# POWER.net
KiCad netlist of a schematic drawn in Altium Designer
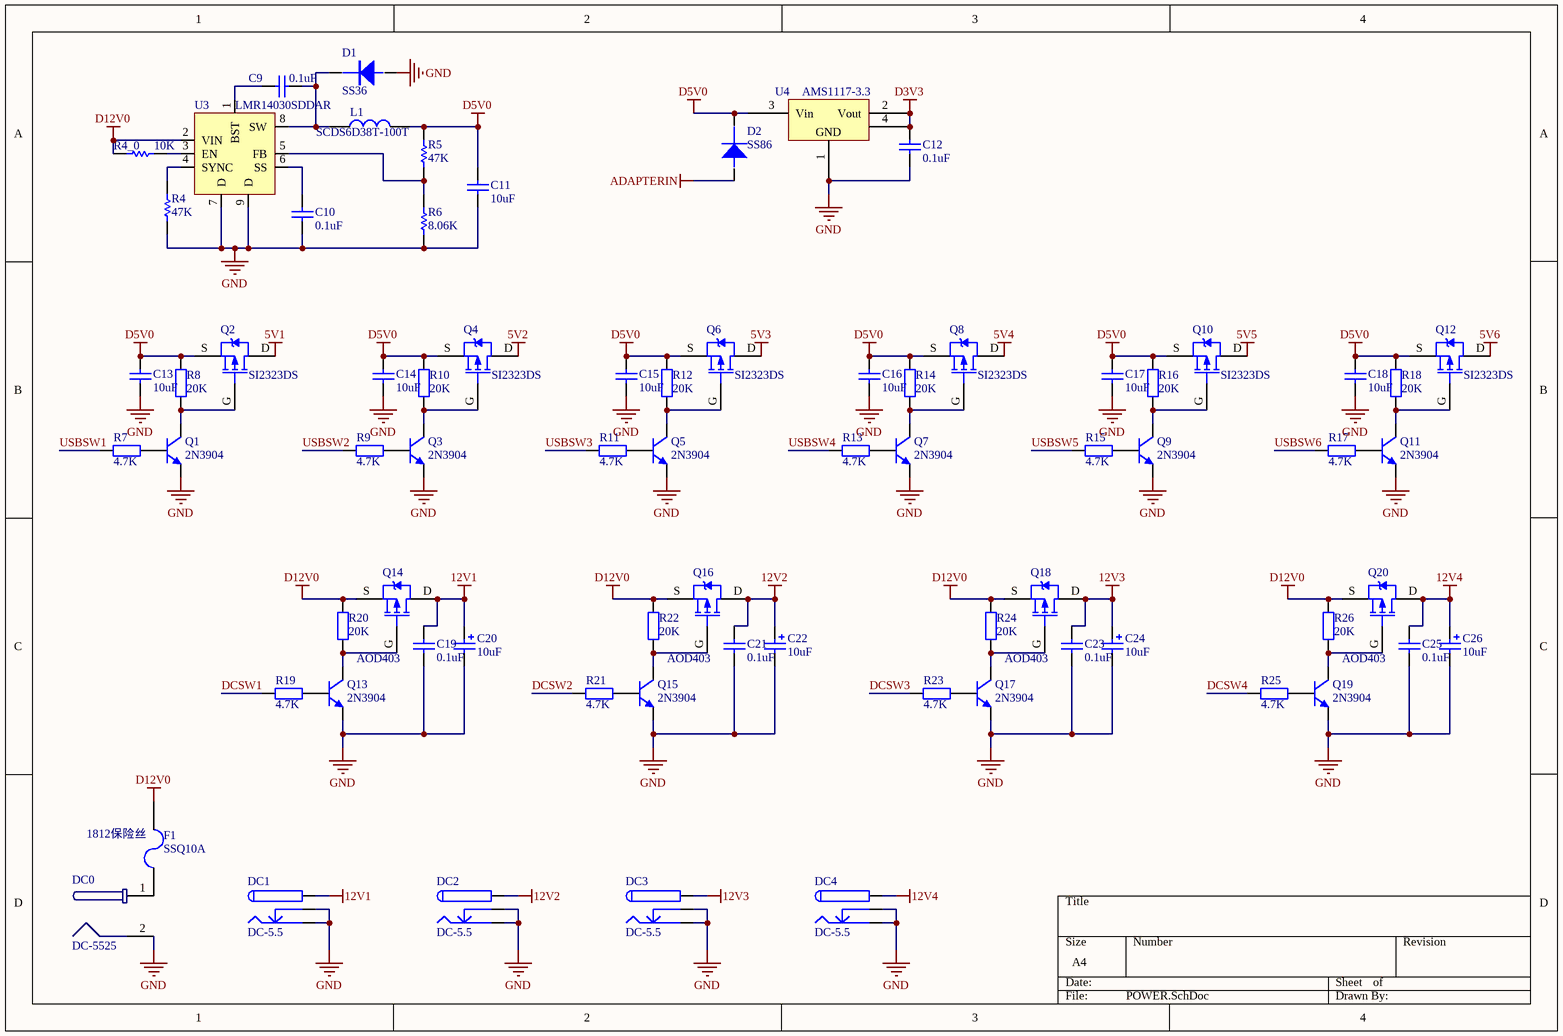
[diagram p0: POWER.SchDoc]

(export (version "E")
  (design (tool "Eeschema 10.0.6"))
  (components
    (comp (ref "C9")
      (value "0.1uF")
      (footprint "0603C")
      (description "Capacitor")
      (fields (field (name "PUBLISHER") "Altium Limited"))
      (libsource (lib "JL_SCH") (part "Cap"))
    )
    (comp (ref "C10")
      (value "0.1uF")
      (footprint "0603C")
      (description "Capacitor")
      (fields (field (name "PUBLISHER") "Altium Limited"))
      (libsource (lib "JL_SCH") (part "Cap"))
    )
    (comp (ref "C11")
      (value "10uF")
      (footprint "3216")
      (description "Capacitor")
      (fields (field (name "PUBLISHER") "Altium Limited"))
      (libsource (lib "JL_SCH") (part "Cap"))
    )
    (comp (ref "C12")
      (value "0.1uF")
      (footprint "0603C")
      (description "Capacitor")
      (fields (field (name "PUBLISHER") "Altium Limited"))
      (libsource (lib "JL_SCH") (part "Cap"))
    )
    (comp (ref "C13")
      (value "10uF")
      (footprint "3216")
      (description "Capacitor")
      (fields (field (name "PUBLISHER") "Altium Limited"))
      (libsource (lib "JL_SCH") (part "Cap"))
    )
    (comp (ref "C14")
      (value "10uF")
      (footprint "3216")
      (description "Capacitor")
      (fields (field (name "PUBLISHER") "Altium Limited"))
      (libsource (lib "JL_SCH") (part "Cap"))
    )
    (comp (ref "C15")
      (value "10uF")
      (footprint "3216")
      (description "Capacitor")
      (fields (field (name "PUBLISHER") "Altium Limited"))
      (libsource (lib "JL_SCH") (part "Cap"))
    )
    (comp (ref "C16")
      (value "10uF")
      (footprint "3216")
      (description "Capacitor")
      (fields (field (name "PUBLISHER") "Altium Limited"))
      (libsource (lib "JL_SCH") (part "Cap"))
    )
    (comp (ref "C17")
      (value "10uF")
      (footprint "3216")
      (description "Capacitor")
      (fields (field (name "PUBLISHER") "Altium Limited"))
      (libsource (lib "JL_SCH") (part "Cap"))
    )
    (comp (ref "C18")
      (value "10uF")
      (footprint "3216")
      (description "Capacitor")
      (fields (field (name "PUBLISHER") "Altium Limited"))
      (libsource (lib "JL_SCH") (part "Cap"))
    )
    (comp (ref "C19")
      (value "0.1uF")
      (footprint "0603C")
      (description "Capacitor")
      (fields (field (name "PUBLISHER") "Altium Limited"))
      (libsource (lib "JL_SCH") (part "Cap"))
    )
    (comp (ref "C20")
      (value "10uF")
      (footprint "3216")
      (description "Polarized Capacitor (Radial)")
      (fields (field (name "PUBLISHER") "Altium Limited"))
      (libsource (lib "JL_SCH") (part "Cap Pol1"))
    )
    (comp (ref "C21")
      (value "0.1uF")
      (footprint "0603C")
      (description "Capacitor")
      (fields (field (name "PUBLISHER") "Altium Limited"))
      (libsource (lib "JL_SCH") (part "Cap"))
    )
    (comp (ref "C22")
      (value "10uF")
      (footprint "3216")
      (description "Polarized Capacitor (Radial)")
      (fields (field (name "PUBLISHER") "Altium Limited"))
      (libsource (lib "JL_SCH") (part "Cap Pol1"))
    )
    (comp (ref "C23")
      (value "0.1uF")
      (footprint "0603C")
      (description "Capacitor")
      (fields (field (name "PUBLISHER") "Altium Limited"))
      (libsource (lib "JL_SCH") (part "Cap"))
    )
    (comp (ref "C24")
      (value "10uF")
      (footprint "3216")
      (description "Polarized Capacitor (Radial)")
      (fields (field (name "PUBLISHER") "Altium Limited"))
      (libsource (lib "JL_SCH") (part "Cap Pol1"))
    )
    (comp (ref "C25")
      (value "0.1uF")
      (footprint "0603C")
      (description "Capacitor")
      (fields (field (name "PUBLISHER") "Altium Limited"))
      (libsource (lib "JL_SCH") (part "Cap"))
    )
    (comp (ref "C26")
      (value "10uF")
      (footprint "3216")
      (description "Polarized Capacitor (Radial)")
      (fields (field (name "PUBLISHER") "Altium Limited"))
      (libsource (lib "JL_SCH") (part "Cap Pol1"))
    )
    (comp (ref "D1")
      (value "SS36")
      (footprint "DO-214AC")
      (description "二极管，3A")
      (libsource (lib "平台原理图symbol图库V1.0") (part "SS36"))
    )
    (comp (ref "D2")
      (value "SS86")
      (footprint "SS34")
      (description "Diode,Vr=60V,If=8.0A,Vf=0.75V,DO-214AB,SS86,8.13x6.22x2.62mm")
      (libsource (lib "Diode") (part "SS86"))
    )
    (comp (ref "DC0") (value "DC-5525") (footprint "DC-5525") (libsource (lib "JL_SCH") (part "DC-5525")))
    (comp (ref "DC1") (value "DC-5.5") (footprint "DC_5.5MM") (libsource (lib "JL_SCH") (part "POWER-5.5")))
    (comp (ref "DC2") (value "DC-5.5") (footprint "DC_5.5MM") (libsource (lib "JL_SCH") (part "POWER-5.5")))
    (comp (ref "DC3") (value "DC-5.5") (footprint "DC_5.5MM") (libsource (lib "JL_SCH") (part "POWER-5.5")))
    (comp (ref "DC4") (value "DC-5.5") (footprint "DC_5.5MM") (libsource (lib "JL_SCH") (part "POWER-5.5")))
    (comp (ref "F1")
      (value "SSQ10A")
      (footprint "1812R")
      (description "Fuse")
      (libsource (lib "JL_SCH") (part "FUSE2"))
    )
    (comp (ref "L1")
      (value "SCDS6D38T-100T")
      (footprint "CD845")
      (description "电感")
      (libsource (lib "TYW_Discrete") (part "SPM6530"))
    )
    (comp (ref "Q1")
      (value "2N3904")
      (footprint "SOT-23")
      (description "NPN General Purpose Amplifier")
      (fields (field (name "PUBLISHER") "Altium Limited"))
      (libsource (lib "JL_SCH") (part "2N3904"))
    )
    (comp (ref "Q2") (value "SI2323DS") (footprint "SIMOS") (libsource (lib "JL_SCH") (part "SI2323")))
    (comp (ref "Q3")
      (value "2N3904")
      (footprint "SOT-23")
      (description "NPN General Purpose Amplifier")
      (fields (field (name "PUBLISHER") "Altium Limited"))
      (libsource (lib "JL_SCH") (part "2N3904"))
    )
    (comp (ref "Q4") (value "SI2323DS") (footprint "SIMOS") (libsource (lib "JL_SCH") (part "SI2323")))
    (comp (ref "Q5")
      (value "2N3904")
      (footprint "SOT-23")
      (description "NPN General Purpose Amplifier")
      (fields (field (name "PUBLISHER") "Altium Limited"))
      (libsource (lib "JL_SCH") (part "2N3904"))
    )
    (comp (ref "Q6") (value "SI2323DS") (footprint "SIMOS") (libsource (lib "JL_SCH") (part "SI2323")))
    (comp (ref "Q7")
      (value "2N3904")
      (footprint "SOT-23")
      (description "NPN General Purpose Amplifier")
      (fields (field (name "PUBLISHER") "Altium Limited"))
      (libsource (lib "JL_SCH") (part "2N3904"))
    )
    (comp (ref "Q8") (value "SI2323DS") (footprint "SIMOS") (libsource (lib "JL_SCH") (part "SI2323")))
    (comp (ref "Q9")
      (value "2N3904")
      (footprint "SOT-23")
      (description "NPN General Purpose Amplifier")
      (fields (field (name "PUBLISHER") "Altium Limited"))
      (libsource (lib "JL_SCH") (part "2N3904"))
    )
    (comp (ref "Q10") (value "SI2323DS") (footprint "SIMOS") (libsource (lib "JL_SCH") (part "SI2323")))
    (comp (ref "Q11")
      (value "2N3904")
      (footprint "SOT-23")
      (description "NPN General Purpose Amplifier")
      (fields (field (name "PUBLISHER") "Altium Limited"))
      (libsource (lib "JL_SCH") (part "2N3904"))
    )
    (comp (ref "Q12") (value "SI2323DS") (footprint "SIMOS") (libsource (lib "JL_SCH") (part "SI2323")))
    (comp (ref "Q13")
      (value "2N3904")
      (footprint "SOT-23")
      (description "NPN General Purpose Amplifier")
      (fields (field (name "PUBLISHER") "Altium Limited"))
      (libsource (lib "JL_SCH") (part "2N3904"))
    )
    (comp (ref "Q14") (value "AOD403") (footprint "TO-252") (libsource (lib "JL_SCH") (part "SI2323")))
    (comp (ref "Q15")
      (value "2N3904")
      (footprint "SOT-23")
      (description "NPN General Purpose Amplifier")
      (fields (field (name "PUBLISHER") "Altium Limited"))
      (libsource (lib "JL_SCH") (part "2N3904"))
    )
    (comp (ref "Q16") (value "AOD403") (footprint "TO-252") (libsource (lib "JL_SCH") (part "SI2323")))
    (comp (ref "Q17")
      (value "2N3904")
      (footprint "SOT-23")
      (description "NPN General Purpose Amplifier")
      (fields (field (name "PUBLISHER") "Altium Limited"))
      (libsource (lib "JL_SCH") (part "2N3904"))
    )
    (comp (ref "Q18") (value "AOD403") (footprint "TO-252") (libsource (lib "JL_SCH") (part "SI2323")))
    (comp (ref "Q19")
      (value "2N3904")
      (footprint "SOT-23")
      (description "NPN General Purpose Amplifier")
      (fields (field (name "PUBLISHER") "Altium Limited"))
      (libsource (lib "JL_SCH") (part "2N3904"))
    )
    (comp (ref "Q20") (value "AOD403") (footprint "TO-252") (libsource (lib "JL_SCH") (part "SI2323")))
    (comp (ref "R4")
      (value "47K")
      (footprint "0603R")
      (description "贴片电阻")
      (fields (field (name "PUBLISHER") "Altium Limited"))
      (libsource (lib "JL_SCH") (part "Res"))
    )
    (comp (ref "R4_0")
      (value "10K")
      (footprint "0603R")
      (description "贴片电阻")
      (fields (field (name "PUBLISHER") "Altium Limited"))
      (libsource (lib "JL_SCH") (part "Res"))
    )
    (comp (ref "R5")
      (value "47K")
      (footprint "0603R")
      (description "贴片电阻")
      (fields (field (name "PUBLISHER") "Altium Limited"))
      (libsource (lib "JL_SCH") (part "Res"))
    )
    (comp (ref "R6")
      (value "8.06K")
      (footprint "0603R")
      (description "贴片电阻")
      (fields (field (name "PUBLISHER") "Altium Limited"))
      (libsource (lib "JL_SCH") (part "Res"))
    )
    (comp (ref "R7")
      (value "4.7K")
      (footprint "0603R")
      (description "Resistor")
      (fields (field (name "PUBLISHER") "Altium Limited"))
      (libsource (lib "") (part "RES_1"))
    )
    (comp (ref "R8")
      (value "20K")
      (footprint "0603R")
      (description "Resistor")
      (fields (field (name "PUBLISHER") "Altium Limited"))
      (libsource (lib "Crazy_PCB") (part "RES"))
    )
    (comp (ref "R9")
      (value "4.7K")
      (footprint "0603R")
      (description "Resistor")
      (fields (field (name "PUBLISHER") "Altium Limited"))
      (libsource (lib "") (part "RES_1"))
    )
    (comp (ref "R10")
      (value "20K")
      (footprint "0603R")
      (description "Resistor")
      (fields (field (name "PUBLISHER") "Altium Limited"))
      (libsource (lib "Crazy_PCB") (part "RES"))
    )
    (comp (ref "R11")
      (value "4.7K")
      (footprint "0603R")
      (description "Resistor")
      (fields (field (name "PUBLISHER") "Altium Limited"))
      (libsource (lib "") (part "RES_1"))
    )
    (comp (ref "R12")
      (value "20K")
      (footprint "0603R")
      (description "Resistor")
      (fields (field (name "PUBLISHER") "Altium Limited"))
      (libsource (lib "Crazy_PCB") (part "RES"))
    )
    (comp (ref "R13")
      (value "4.7K")
      (footprint "0603R")
      (description "Resistor")
      (fields (field (name "PUBLISHER") "Altium Limited"))
      (libsource (lib "") (part "RES_1"))
    )
    (comp (ref "R14")
      (value "20K")
      (footprint "0603R")
      (description "Resistor")
      (fields (field (name "PUBLISHER") "Altium Limited"))
      (libsource (lib "Crazy_PCB") (part "RES"))
    )
    (comp (ref "R15")
      (value "4.7K")
      (footprint "0603R")
      (description "Resistor")
      (fields (field (name "PUBLISHER") "Altium Limited"))
      (libsource (lib "") (part "RES_1"))
    )
    (comp (ref "R16")
      (value "20K")
      (footprint "0603R")
      (description "Resistor")
      (fields (field (name "PUBLISHER") "Altium Limited"))
      (libsource (lib "Crazy_PCB") (part "RES"))
    )
    (comp (ref "R17")
      (value "4.7K")
      (footprint "0603R")
      (description "Resistor")
      (fields (field (name "PUBLISHER") "Altium Limited"))
      (libsource (lib "") (part "RES_1"))
    )
    (comp (ref "R18")
      (value "20K")
      (footprint "0603R")
      (description "Resistor")
      (fields (field (name "PUBLISHER") "Altium Limited"))
      (libsource (lib "Crazy_PCB") (part "RES"))
    )
    (comp (ref "R19")
      (value "4.7K")
      (footprint "0603R")
      (description "Resistor")
      (fields (field (name "PUBLISHER") "Altium Limited"))
      (libsource (lib "") (part "RES_1"))
    )
    (comp (ref "R20")
      (value "20K")
      (footprint "0603R")
      (description "Resistor")
      (fields (field (name "PUBLISHER") "Altium Limited"))
      (libsource (lib "Crazy_PCB") (part "RES"))
    )
    (comp (ref "R21")
      (value "4.7K")
      (footprint "0603R")
      (description "Resistor")
      (fields (field (name "PUBLISHER") "Altium Limited"))
      (libsource (lib "") (part "RES_1"))
    )
    (comp (ref "R22")
      (value "20K")
      (footprint "0603R")
      (description "Resistor")
      (fields (field (name "PUBLISHER") "Altium Limited"))
      (libsource (lib "Crazy_PCB") (part "RES"))
    )
    (comp (ref "R23")
      (value "4.7K")
      (footprint "0603R")
      (description "Resistor")
      (fields (field (name "PUBLISHER") "Altium Limited"))
      (libsource (lib "") (part "RES_1"))
    )
    (comp (ref "R24")
      (value "20K")
      (footprint "0603R")
      (description "Resistor")
      (fields (field (name "PUBLISHER") "Altium Limited"))
      (libsource (lib "Crazy_PCB") (part "RES"))
    )
    (comp (ref "R25")
      (value "4.7K")
      (footprint "0603R")
      (description "Resistor")
      (fields (field (name "PUBLISHER") "Altium Limited"))
      (libsource (lib "") (part "RES_1"))
    )
    (comp (ref "R26")
      (value "20K")
      (footprint "0603R")
      (description "Resistor")
      (fields (field (name "PUBLISHER") "Altium Limited"))
      (libsource (lib "Crazy_PCB") (part "RES"))
    )
    (comp (ref "U3")
      (value "LMR14030SDDAR")
      (footprint "LMR14030")
      (libsource (lib "JL_SCH") (part "LMR14030"))
    )
    (comp (ref "U4") (value "AMS1117-3.3") (footprint "SOT223") (libsource (lib "JL_SCH") (part "SPX1117")))
  )
  (nets
    (net (code "1") (name "/DCSW1") (class "Default")
      (node (ref "R19") (pin "1") (pinfunction "1_1") (pintype "passive"))
    )
    (net (code "2") (name "/DCSW2") (class "Default")
      (node (ref "R21") (pin "1") (pinfunction "1_1") (pintype "passive"))
    )
    (net (code "3") (name "/DCSW3") (class "Default")
      (node (ref "R23") (pin "1") (pinfunction "1_1") (pintype "passive"))
    )
    (net (code "4") (name "/DCSW4") (class "Default")
      (node (ref "R25") (pin "1") (pinfunction "1_1") (pintype "passive"))
    )
    (net (code "5") (name "/USBSW1") (class "Default")
      (node (ref "R7") (pin "1") (pinfunction "1_1") (pintype "passive"))
    )
    (net (code "6") (name "/USBSW2") (class "Default")
      (node (ref "R9") (pin "1") (pinfunction "1_1") (pintype "passive"))
    )
    (net (code "7") (name "/USBSW3") (class "Default")
      (node (ref "R11") (pin "1") (pinfunction "1_1") (pintype "passive"))
    )
    (net (code "8") (name "/USBSW4") (class "Default")
      (node (ref "R13") (pin "1") (pinfunction "1_1") (pintype "passive"))
    )
    (net (code "9") (name "/USBSW5") (class "Default")
      (node (ref "R15") (pin "1") (pinfunction "1_1") (pintype "passive"))
    )
    (net (code "10") (name "/USBSW6") (class "Default")
      (node (ref "R17") (pin "1") (pinfunction "1_1") (pintype "passive"))
    )
    (net (code "11") (name "5V1") (class "Default")
      (node (ref "Q2") (pin "D") (pinfunction "D_D") (pintype "passive"))
    )
    (net (code "12") (name "5V2") (class "Default")
      (node (ref "Q4") (pin "D") (pinfunction "D_D") (pintype "passive"))
    )
    (net (code "13") (name "5V3") (class "Default")
      (node (ref "Q6") (pin "D") (pinfunction "D_D") (pintype "passive"))
    )
    (net (code "14") (name "5V4") (class "Default")
      (node (ref "Q8") (pin "D") (pinfunction "D_D") (pintype "passive"))
    )
    (net (code "15") (name "5V5") (class "Default")
      (node (ref "Q10") (pin "D") (pinfunction "D_D") (pintype "passive"))
    )
    (net (code "16") (name "5V6") (class "Default")
      (node (ref "Q12") (pin "D") (pinfunction "D_D") (pintype "passive"))
    )
    (net (code "17") (name "12V1") (class "Default")
      (node (ref "C19") (pin "1") (pinfunction "1_1") (pintype "passive"))
      (node (ref "C20") (pin "1") (pinfunction "1_1") (pintype "passive"))
      (node (ref "DC1") (pin "1") (pinfunction "1_1") (pintype "power_in"))
      (node (ref "Q14") (pin "D") (pinfunction "D_D") (pintype "passive"))
    )
    (net (code "18") (name "12V2") (class "Default")
      (node (ref "C21") (pin "1") (pinfunction "1_1") (pintype "passive"))
      (node (ref "C22") (pin "1") (pinfunction "1_1") (pintype "passive"))
      (node (ref "DC2") (pin "1") (pinfunction "1_1") (pintype "power_in"))
      (node (ref "Q16") (pin "D") (pinfunction "D_D") (pintype "passive"))
    )
    (net (code "19") (name "12V3") (class "Default")
      (node (ref "C23") (pin "1") (pinfunction "1_1") (pintype "passive"))
      (node (ref "C24") (pin "1") (pinfunction "1_1") (pintype "passive"))
      (node (ref "DC3") (pin "1") (pinfunction "1_1") (pintype "power_in"))
      (node (ref "Q18") (pin "D") (pinfunction "D_D") (pintype "passive"))
    )
    (net (code "20") (name "12V4") (class "Default")
      (node (ref "C25") (pin "1") (pinfunction "1_1") (pintype "passive"))
      (node (ref "C26") (pin "1") (pinfunction "1_1") (pintype "passive"))
      (node (ref "DC4") (pin "1") (pinfunction "1_1") (pintype "power_in"))
      (node (ref "Q20") (pin "D") (pinfunction "D_D") (pintype "passive"))
    )
    (net (code "21") (name "ADAPTERIN") (class "Default")
      (node (ref "D2") (pin "1") (pinfunction "1_1") (pintype "passive"))
    )
    (net (code "22") (name "D3V3") (class "Default")
      (node (ref "C12") (pin "2") (pinfunction "2_2") (pintype "passive"))
      (node (ref "U4") (pin "2") (pinfunction "Vout_2") (pintype "passive"))
      (node (ref "U4") (pin "4") (pintype "passive"))
    )
    (net (code "23") (name "D5V0") (class "Default")
      (node (ref "C11") (pin "1") (pinfunction "1_1") (pintype "passive"))
      (node (ref "C13") (pin "1") (pinfunction "1_1") (pintype "passive"))
      (node (ref "C14") (pin "1") (pinfunction "1_1") (pintype "passive"))
      (node (ref "C15") (pin "1") (pinfunction "1_1") (pintype "passive"))
      (node (ref "C16") (pin "1") (pinfunction "1_1") (pintype "passive"))
      (node (ref "C17") (pin "1") (pinfunction "1_1") (pintype "passive"))
      (node (ref "C18") (pin "1") (pinfunction "1_1") (pintype "passive"))
      (node (ref "D2") (pin "2") (pinfunction "2_2") (pintype "passive"))
      (node (ref "L1") (pin "2") (pinfunction "2_2") (pintype "passive"))
      (node (ref "Q10") (pin "S") (pinfunction "S_S") (pintype "passive"))
      (node (ref "Q12") (pin "S") (pinfunction "S_S") (pintype "passive"))
      (node (ref "Q2") (pin "S") (pinfunction "S_S") (pintype "passive"))
      (node (ref "Q4") (pin "S") (pinfunction "S_S") (pintype "passive"))
      (node (ref "Q6") (pin "S") (pinfunction "S_S") (pintype "passive"))
      (node (ref "Q8") (pin "S") (pinfunction "S_S") (pintype "passive"))
      (node (ref "R10") (pin "1") (pinfunction "1_1") (pintype "passive"))
      (node (ref "R12") (pin "1") (pinfunction "1_1") (pintype "passive"))
      (node (ref "R14") (pin "1") (pinfunction "1_1") (pintype "passive"))
      (node (ref "R16") (pin "1") (pinfunction "1_1") (pintype "passive"))
      (node (ref "R18") (pin "1") (pinfunction "1_1") (pintype "passive"))
      (node (ref "R5") (pin "1") (pinfunction "1_1") (pintype "passive"))
      (node (ref "R8") (pin "1") (pinfunction "1_1") (pintype "passive"))
      (node (ref "U4") (pin "3") (pinfunction "Vin_3") (pintype "passive"))
    )
    (net (code "24") (name "D12V0") (class "Default")
      (node (ref "F1") (pin "2") (pinfunction "2_2") (pintype "passive"))
      (node (ref "Q14") (pin "S") (pinfunction "S_S") (pintype "passive"))
      (node (ref "Q16") (pin "S") (pinfunction "S_S") (pintype "passive"))
      (node (ref "Q18") (pin "S") (pinfunction "S_S") (pintype "passive"))
      (node (ref "Q20") (pin "S") (pinfunction "S_S") (pintype "passive"))
      (node (ref "R20") (pin "1") (pinfunction "1_1") (pintype "passive"))
      (node (ref "R22") (pin "1") (pinfunction "1_1") (pintype "passive"))
      (node (ref "R24") (pin "1") (pinfunction "1_1") (pintype "passive"))
      (node (ref "R26") (pin "1") (pinfunction "1_1") (pintype "passive"))
      (node (ref "R4_0") (pin "2") (pinfunction "2_2") (pintype "passive"))
      (node (ref "U3") (pin "2") (pinfunction "VIN_2") (pintype "passive"))
    )
    (net (code "25") (name "GND") (class "Default")
      (node (ref "C10") (pin "1") (pinfunction "1_1") (pintype "passive"))
      (node (ref "C11") (pin "2") (pinfunction "2_2") (pintype "passive"))
      (node (ref "C12") (pin "1") (pinfunction "1_1") (pintype "passive"))
      (node (ref "C13") (pin "2") (pinfunction "2_2") (pintype "passive"))
      (node (ref "C14") (pin "2") (pinfunction "2_2") (pintype "passive"))
      (node (ref "C15") (pin "2") (pinfunction "2_2") (pintype "passive"))
      (node (ref "C16") (pin "2") (pinfunction "2_2") (pintype "passive"))
      (node (ref "C17") (pin "2") (pinfunction "2_2") (pintype "passive"))
      (node (ref "C18") (pin "2") (pinfunction "2_2") (pintype "passive"))
      (node (ref "C19") (pin "2") (pinfunction "2_2") (pintype "passive"))
      (node (ref "C20") (pin "2") (pinfunction "2_2") (pintype "passive"))
      (node (ref "C21") (pin "2") (pinfunction "2_2") (pintype "passive"))
      (node (ref "C22") (pin "2") (pinfunction "2_2") (pintype "passive"))
      (node (ref "C23") (pin "2") (pinfunction "2_2") (pintype "passive"))
      (node (ref "C24") (pin "2") (pinfunction "2_2") (pintype "passive"))
      (node (ref "C25") (pin "2") (pinfunction "2_2") (pintype "passive"))
      (node (ref "C26") (pin "2") (pinfunction "2_2") (pintype "passive"))
      (node (ref "D1") (pin "1") (pinfunction "1_1") (pintype "passive"))
      (node (ref "DC0") (pin "2") (pinfunction "2_2") (pintype "passive"))
      (node (ref "DC1") (pin "2") (pinfunction "2_2") (pintype "power_in"))
      (node (ref "DC1") (pin "3") (pinfunction "3_3") (pintype "power_in"))
      (node (ref "DC2") (pin "2") (pinfunction "2_2") (pintype "power_in"))
      (node (ref "DC2") (pin "3") (pinfunction "3_3") (pintype "power_in"))
      (node (ref "DC3") (pin "2") (pinfunction "2_2") (pintype "power_in"))
      (node (ref "DC3") (pin "3") (pinfunction "3_3") (pintype "power_in"))
      (node (ref "DC4") (pin "2") (pinfunction "2_2") (pintype "power_in"))
      (node (ref "DC4") (pin "3") (pinfunction "3_3") (pintype "power_in"))
      (node (ref "Q1") (pin "E") (pinfunction "2_E") (pintype "passive"))
      (node (ref "Q11") (pin "E") (pinfunction "2_E") (pintype "passive"))
      (node (ref "Q13") (pin "E") (pinfunction "2_E") (pintype "passive"))
      (node (ref "Q15") (pin "E") (pinfunction "2_E") (pintype "passive"))
      (node (ref "Q17") (pin "E") (pinfunction "2_E") (pintype "passive"))
      (node (ref "Q19") (pin "E") (pinfunction "2_E") (pintype "passive"))
      (node (ref "Q3") (pin "E") (pinfunction "2_E") (pintype "passive"))
      (node (ref "Q5") (pin "E") (pinfunction "2_E") (pintype "passive"))
      (node (ref "Q7") (pin "E") (pinfunction "2_E") (pintype "passive"))
      (node (ref "Q9") (pin "E") (pinfunction "2_E") (pintype "passive"))
      (node (ref "R4") (pin "2") (pinfunction "2_2") (pintype "passive"))
      (node (ref "R6") (pin "2") (pinfunction "2_2") (pintype "passive"))
      (node (ref "U3") (pin "7") (pinfunction "D_7") (pintype "passive"))
      (node (ref "U3") (pin "9") (pinfunction "D_9") (pintype "passive"))
      (node (ref "U4") (pin "1") (pintype "passive"))
    )
    (net (code "26") (name "Net-(DC0-Pad1)") (class "Default")
      (node (ref "DC0") (pin "1") (pinfunction "1_1") (pintype "passive"))
      (node (ref "F1") (pin "1") (pinfunction "1_1") (pintype "passive"))
    )
    (net (code "27") (name "Net-(Q1-1)") (class "Default")
      (node (ref "Q1") (pin "B") (pinfunction "1_B") (pintype "passive"))
      (node (ref "R7") (pin "2") (pinfunction "2_2") (pintype "passive"))
    )
    (net (code "28") (name "Net-(Q1-3)") (class "Default")
      (node (ref "Q1") (pin "C") (pinfunction "3_C") (pintype "passive"))
      (node (ref "Q2") (pin "G") (pinfunction "G_G") (pintype "passive"))
      (node (ref "R8") (pin "2") (pinfunction "2_2") (pintype "passive"))
    )
    (net (code "29") (name "Net-(Q3-1)") (class "Default")
      (node (ref "Q3") (pin "B") (pinfunction "1_B") (pintype "passive"))
      (node (ref "R9") (pin "2") (pinfunction "2_2") (pintype "passive"))
    )
    (net (code "30") (name "Net-(Q3-3)") (class "Default")
      (node (ref "Q3") (pin "C") (pinfunction "3_C") (pintype "passive"))
      (node (ref "Q4") (pin "G") (pinfunction "G_G") (pintype "passive"))
      (node (ref "R10") (pin "2") (pinfunction "2_2") (pintype "passive"))
    )
    (net (code "31") (name "Net-(Q5-1)") (class "Default")
      (node (ref "Q5") (pin "B") (pinfunction "1_B") (pintype "passive"))
      (node (ref "R11") (pin "2") (pinfunction "2_2") (pintype "passive"))
    )
    (net (code "32") (name "Net-(Q5-3)") (class "Default")
      (node (ref "Q5") (pin "C") (pinfunction "3_C") (pintype "passive"))
      (node (ref "Q6") (pin "G") (pinfunction "G_G") (pintype "passive"))
      (node (ref "R12") (pin "2") (pinfunction "2_2") (pintype "passive"))
    )
    (net (code "33") (name "Net-(Q7-1)") (class "Default")
      (node (ref "Q7") (pin "B") (pinfunction "1_B") (pintype "passive"))
      (node (ref "R13") (pin "2") (pinfunction "2_2") (pintype "passive"))
    )
    (net (code "34") (name "Net-(Q7-3)") (class "Default")
      (node (ref "Q7") (pin "C") (pinfunction "3_C") (pintype "passive"))
      (node (ref "Q8") (pin "G") (pinfunction "G_G") (pintype "passive"))
      (node (ref "R14") (pin "2") (pinfunction "2_2") (pintype "passive"))
    )
    (net (code "35") (name "Net-(Q9-1)") (class "Default")
      (node (ref "Q9") (pin "B") (pinfunction "1_B") (pintype "passive"))
      (node (ref "R15") (pin "2") (pinfunction "2_2") (pintype "passive"))
    )
    (net (code "36") (name "Net-(Q9-3)") (class "Default")
      (node (ref "Q10") (pin "G") (pinfunction "G_G") (pintype "passive"))
      (node (ref "Q9") (pin "C") (pinfunction "3_C") (pintype "passive"))
      (node (ref "R16") (pin "2") (pinfunction "2_2") (pintype "passive"))
    )
    (net (code "37") (name "Net-(Q11-1)") (class "Default")
      (node (ref "Q11") (pin "B") (pinfunction "1_B") (pintype "passive"))
      (node (ref "R17") (pin "2") (pinfunction "2_2") (pintype "passive"))
    )
    (net (code "38") (name "Net-(Q11-3)") (class "Default")
      (node (ref "Q11") (pin "C") (pinfunction "3_C") (pintype "passive"))
      (node (ref "Q12") (pin "G") (pinfunction "G_G") (pintype "passive"))
      (node (ref "R18") (pin "2") (pinfunction "2_2") (pintype "passive"))
    )
    (net (code "39") (name "Net-(Q13-1)") (class "Default")
      (node (ref "Q13") (pin "B") (pinfunction "1_B") (pintype "passive"))
      (node (ref "R19") (pin "2") (pinfunction "2_2") (pintype "passive"))
    )
    (net (code "40") (name "Net-(Q13-3)") (class "Default")
      (node (ref "Q13") (pin "C") (pinfunction "3_C") (pintype "passive"))
      (node (ref "Q14") (pin "G") (pinfunction "G_G") (pintype "passive"))
      (node (ref "R20") (pin "2") (pinfunction "2_2") (pintype "passive"))
    )
    (net (code "41") (name "Net-(Q15-1)") (class "Default")
      (node (ref "Q15") (pin "B") (pinfunction "1_B") (pintype "passive"))
      (node (ref "R21") (pin "2") (pinfunction "2_2") (pintype "passive"))
    )
    (net (code "42") (name "Net-(Q15-3)") (class "Default")
      (node (ref "Q15") (pin "C") (pinfunction "3_C") (pintype "passive"))
      (node (ref "Q16") (pin "G") (pinfunction "G_G") (pintype "passive"))
      (node (ref "R22") (pin "2") (pinfunction "2_2") (pintype "passive"))
    )
    (net (code "43") (name "Net-(Q17-1)") (class "Default")
      (node (ref "Q17") (pin "B") (pinfunction "1_B") (pintype "passive"))
      (node (ref "R23") (pin "2") (pinfunction "2_2") (pintype "passive"))
    )
    (net (code "44") (name "Net-(Q17-3)") (class "Default")
      (node (ref "Q17") (pin "C") (pinfunction "3_C") (pintype "passive"))
      (node (ref "Q18") (pin "G") (pinfunction "G_G") (pintype "passive"))
      (node (ref "R24") (pin "2") (pinfunction "2_2") (pintype "passive"))
    )
    (net (code "45") (name "Net-(Q19-1)") (class "Default")
      (node (ref "Q19") (pin "B") (pinfunction "1_B") (pintype "passive"))
      (node (ref "R25") (pin "2") (pinfunction "2_2") (pintype "passive"))
    )
    (net (code "46") (name "Net-(Q19-3)") (class "Default")
      (node (ref "Q19") (pin "C") (pinfunction "3_C") (pintype "passive"))
      (node (ref "Q20") (pin "G") (pinfunction "G_G") (pintype "passive"))
      (node (ref "R26") (pin "2") (pinfunction "2_2") (pintype "passive"))
    )
    (net (code "47") (name "Net-(U3-BST)") (class "Default")
      (node (ref "C9") (pin "2") (pinfunction "2_2") (pintype "passive"))
      (node (ref "U3") (pin "1") (pinfunction "BST_1") (pintype "passive"))
    )
    (net (code "48") (name "Net-(U3-EN)") (class "Default")
      (node (ref "R4_0") (pin "1") (pinfunction "1_1") (pintype "passive"))
      (node (ref "U3") (pin "3") (pinfunction "EN_3") (pintype "passive"))
    )
    (net (code "49") (name "Net-(U3-FB)") (class "Default")
      (node (ref "R5") (pin "2") (pinfunction "2_2") (pintype "passive"))
      (node (ref "R6") (pin "1") (pinfunction "1_1") (pintype "passive"))
      (node (ref "U3") (pin "5") (pinfunction "FB_5") (pintype "passive"))
    )
    (net (code "50") (name "Net-(U3-SS)") (class "Default")
      (node (ref "C10") (pin "2") (pinfunction "2_2") (pintype "passive"))
      (node (ref "U3") (pin "6") (pinfunction "SS_6") (pintype "passive"))
    )
    (net (code "51") (name "Net-(U3-SW)") (class "Default")
      (node (ref "C9") (pin "1") (pinfunction "1_1") (pintype "passive"))
      (node (ref "D1") (pin "2") (pinfunction "2_2") (pintype "passive"))
      (node (ref "L1") (pin "1") (pinfunction "1_1") (pintype "passive"))
      (node (ref "U3") (pin "8") (pinfunction "SW_8") (pintype "passive"))
    )
    (net (code "52") (name "Net-(U3-SYNC)") (class "Default")
      (node (ref "R4") (pin "1") (pinfunction "1_1") (pintype "passive"))
      (node (ref "U3") (pin "4") (pinfunction "SYNC_4") (pintype "passive"))
    )
  )
)
